# 11_iMX_8X_SPI_ADC.net
KiCad netlist of a schematic drawn in Altium Designer
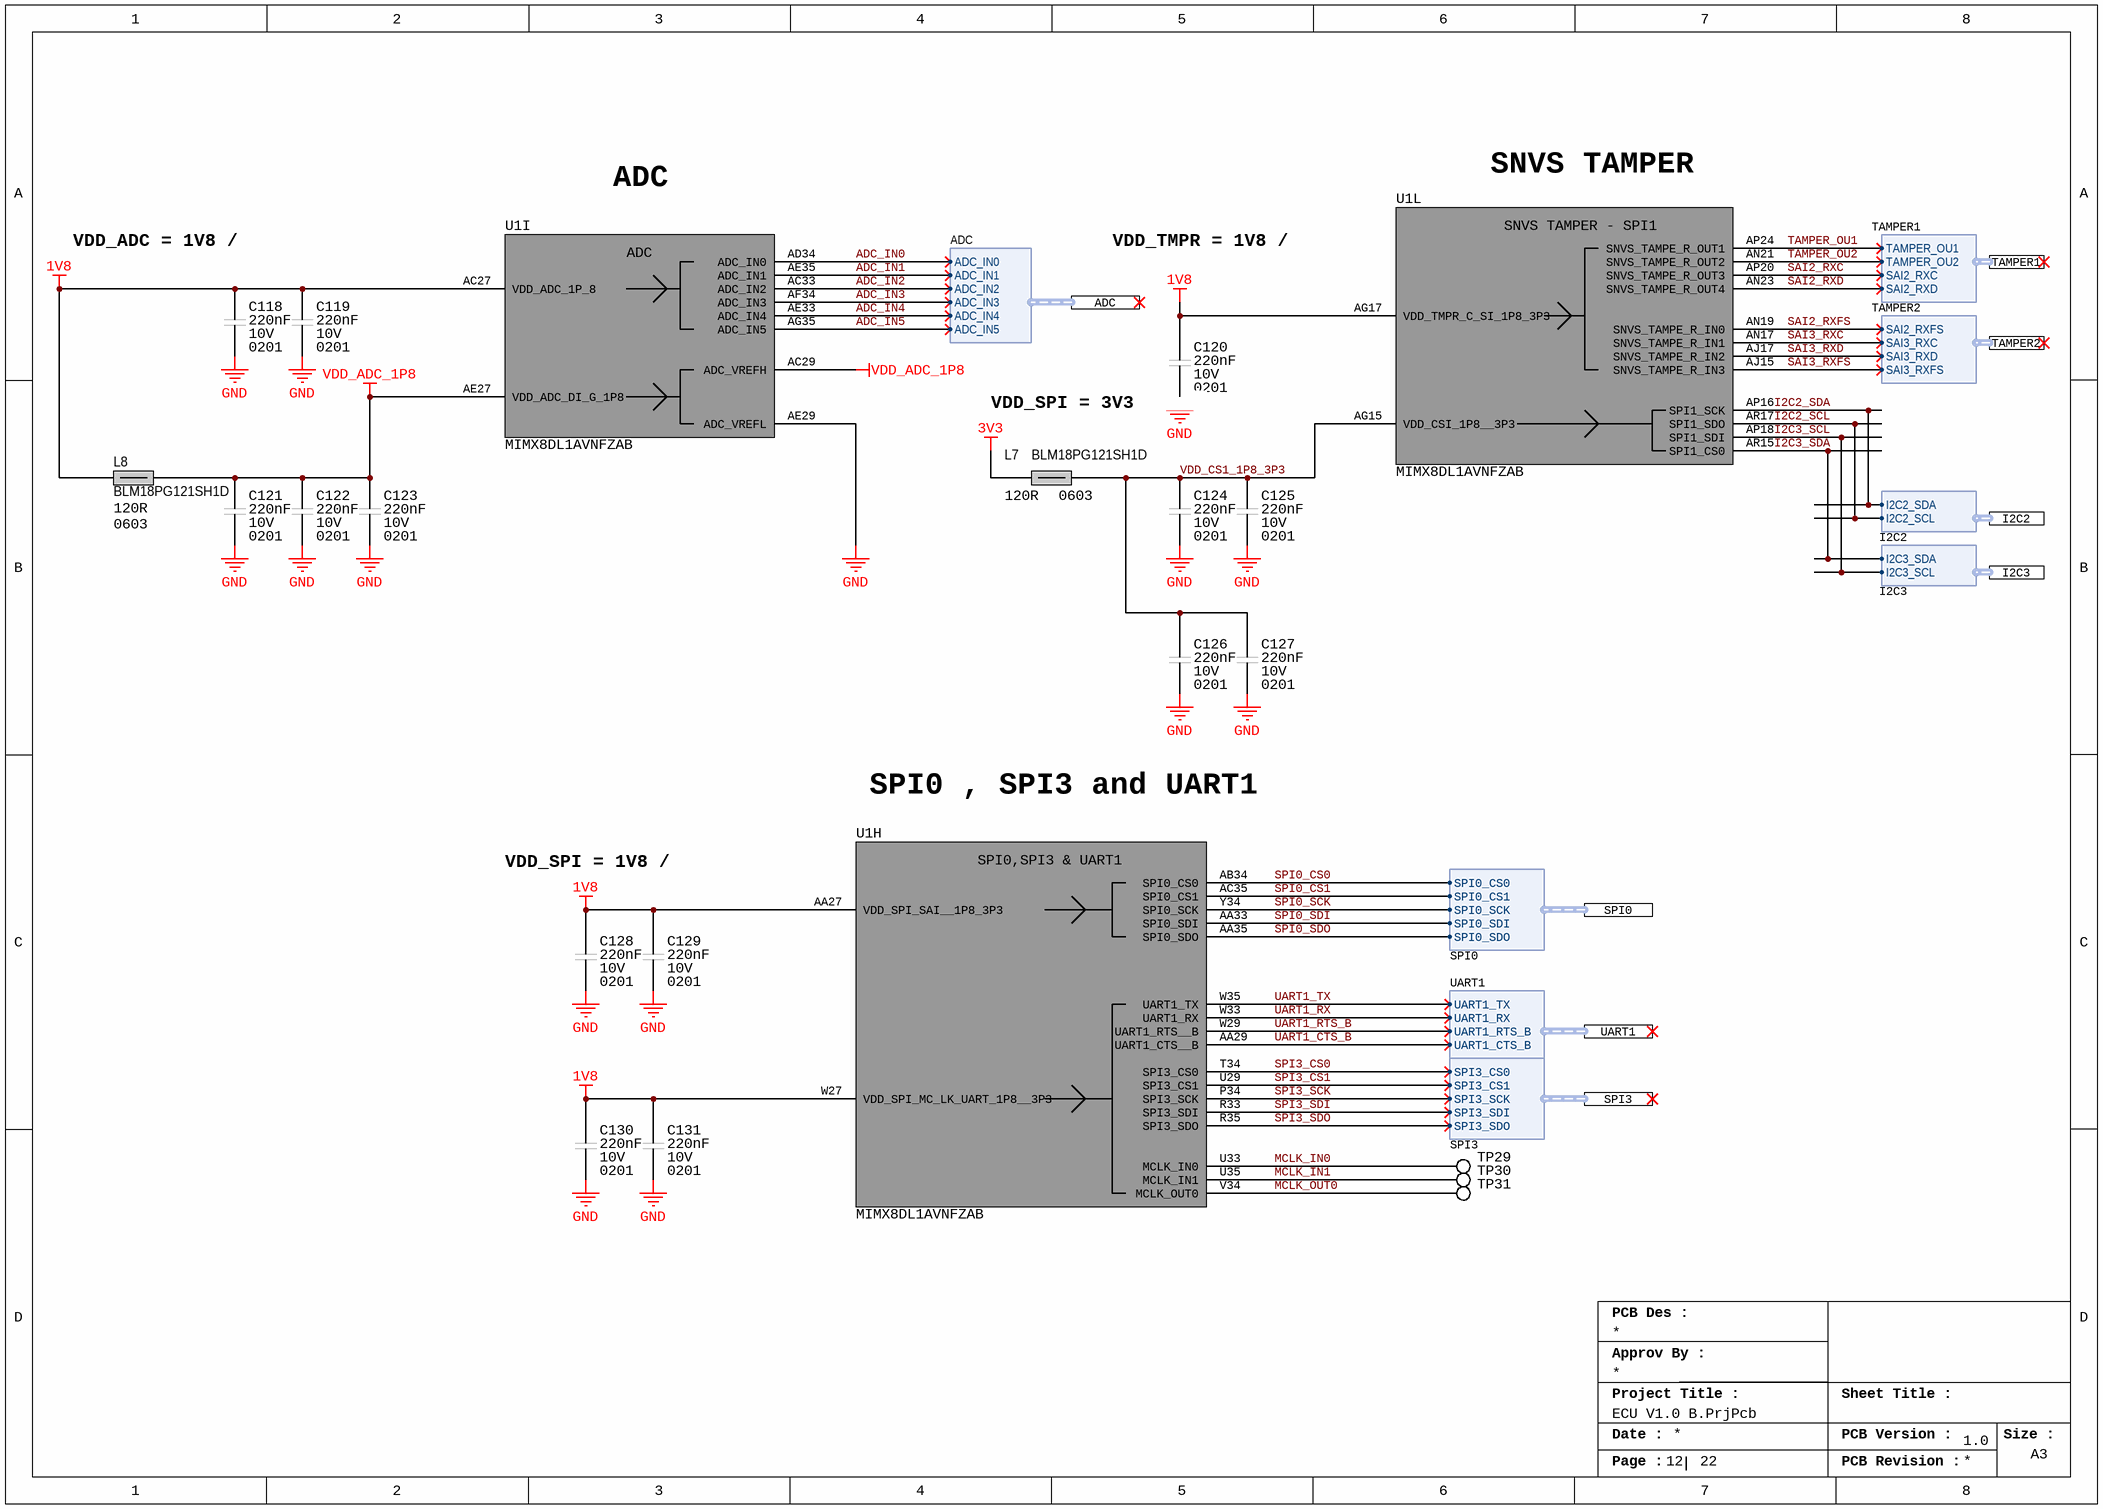
[diagram p0: 11_iMX 8X_SPI & ADC.SchDoc]

(export (version "E")
  (design (tool "Eeschema 10.0.6"))
  (components
    (comp (ref "C118")
      (value "LMK063BJ224MP-F")
      (footprint "CAP_0201_CAPC0603X03N")
      (description "Multilayer Ceramic Capacitors (High dielectric type), 10V, 0.22 uF, ± 20 %, 0201, X5R, RoHS")
      (fields
        (field (name "MANUFACTURER") "Taiyo Yuden")
        (field (name "TOLERANCE") "20%")
        (field (name "VOLTAGE RATING (DC)") "10V")
        (field (name "CAPACITANCE") "220nF")
        (field (name "CASE/PACKAGE") "0201")
      )
      (libsource (lib "Electronic Devices_LIB") (part "CAP_0.22UF_10V_X5R_0201"))
    )
    (comp (ref "C119")
      (value "LMK063BJ224MP-F")
      (footprint "CAP_0201_CAPC0603X03N")
      (description "Multilayer Ceramic Capacitors (High dielectric type), 10V, 0.22 uF, ± 20 %, 0201, X5R, RoHS")
      (fields
        (field (name "MANUFACTURER") "Taiyo Yuden")
        (field (name "TOLERANCE") "20%")
        (field (name "VOLTAGE RATING (DC)") "10V")
        (field (name "CAPACITANCE") "220nF")
        (field (name "CASE/PACKAGE") "0201")
      )
      (libsource (lib "Electronic Devices_LIB") (part "CAP_0.22UF_10V_X5R_0201"))
    )
    (comp (ref "C120")
      (value "LMK063BJ224MP-F")
      (footprint "CAP_0201_CAPC0603X03N")
      (description "Multilayer Ceramic Capacitors (High dielectric type), 10V, 0.22 uF, ± 20 %, 0201, X5R, RoHS")
      (fields
        (field (name "MANUFACTURER") "Taiyo Yuden")
        (field (name "TOLERANCE") "20%")
        (field (name "VOLTAGE RATING (DC)") "10V")
        (field (name "CAPACITANCE") "220nF")
        (field (name "CASE/PACKAGE") "0201")
      )
      (libsource (lib "Electronic Devices_LIB") (part "CAP_0.22UF_10V_X5R_0201"))
    )
    (comp (ref "C121")
      (value "LMK063BJ224MP-F")
      (footprint "CAP_0201_CAPC0603X03N")
      (description "Multilayer Ceramic Capacitors (High dielectric type), 10V, 0.22 uF, ± 20 %, 0201, X5R, RoHS")
      (fields
        (field (name "MANUFACTURER") "Taiyo Yuden")
        (field (name "TOLERANCE") "20%")
        (field (name "VOLTAGE RATING (DC)") "10V")
        (field (name "CAPACITANCE") "220nF")
        (field (name "CASE/PACKAGE") "0201")
      )
      (libsource (lib "Electronic Devices_LIB") (part "CAP_0.22UF_10V_X5R_0201"))
    )
    (comp (ref "C122")
      (value "LMK063BJ224MP-F")
      (footprint "CAP_0201_CAPC0603X03N")
      (description "Multilayer Ceramic Capacitors (High dielectric type), 10V, 0.22 uF, ± 20 %, 0201, X5R, RoHS")
      (fields
        (field (name "MANUFACTURER") "Taiyo Yuden")
        (field (name "TOLERANCE") "20%")
        (field (name "VOLTAGE RATING (DC)") "10V")
        (field (name "CAPACITANCE") "220nF")
        (field (name "CASE/PACKAGE") "0201")
      )
      (libsource (lib "Electronic Devices_LIB") (part "CAP_0.22UF_10V_X5R_0201"))
    )
    (comp (ref "C123")
      (value "LMK063BJ224MP-F")
      (footprint "CAP_0201_CAPC0603X03N")
      (description "Multilayer Ceramic Capacitors (High dielectric type), 10V, 0.22 uF, ± 20 %, 0201, X5R, RoHS")
      (fields
        (field (name "MANUFACTURER") "Taiyo Yuden")
        (field (name "TOLERANCE") "20%")
        (field (name "VOLTAGE RATING (DC)") "10V")
        (field (name "CAPACITANCE") "220nF")
        (field (name "CASE/PACKAGE") "0201")
      )
      (libsource (lib "Electronic Devices_LIB") (part "CAP_0.22UF_10V_X5R_0201"))
    )
    (comp (ref "C124")
      (value "LMK063BJ224MP-F")
      (footprint "CAP_0201_CAPC0603X03N")
      (description "Multilayer Ceramic Capacitors (High dielectric type), 10V, 0.22 uF, ± 20 %, 0201, X5R, RoHS")
      (fields
        (field (name "MANUFACTURER") "Taiyo Yuden")
        (field (name "TOLERANCE") "20%")
        (field (name "VOLTAGE RATING (DC)") "10V")
        (field (name "CAPACITANCE") "220nF")
        (field (name "CASE/PACKAGE") "0201")
      )
      (libsource (lib "Electronic Devices_LIB") (part "CAP_0.22UF_10V_X5R_0201"))
    )
    (comp (ref "C125")
      (value "LMK063BJ224MP-F")
      (footprint "CAP_0201_CAPC0603X03N")
      (description "Multilayer Ceramic Capacitors (High dielectric type), 10V, 0.22 uF, ± 20 %, 0201, X5R, RoHS")
      (fields
        (field (name "MANUFACTURER") "Taiyo Yuden")
        (field (name "TOLERANCE") "20%")
        (field (name "VOLTAGE RATING (DC)") "10V")
        (field (name "CAPACITANCE") "220nF")
        (field (name "CASE/PACKAGE") "0201")
      )
      (libsource (lib "Electronic Devices_LIB") (part "CAP_0.22UF_10V_X5R_0201"))
    )
    (comp (ref "C126")
      (value "LMK063BJ224MP-F")
      (footprint "CAP_0201_CAPC0603X03N")
      (description "Multilayer Ceramic Capacitors (High dielectric type), 10V, 0.22 uF, ± 20 %, 0201, X5R, RoHS")
      (fields
        (field (name "MANUFACTURER") "Taiyo Yuden")
        (field (name "TOLERANCE") "20%")
        (field (name "VOLTAGE RATING (DC)") "10V")
        (field (name "CAPACITANCE") "220nF")
        (field (name "CASE/PACKAGE") "0201")
      )
      (libsource (lib "Electronic Devices_LIB") (part "CAP_0.22UF_10V_X5R_0201"))
    )
    (comp (ref "C127")
      (value "LMK063BJ224MP-F")
      (footprint "CAP_0201_CAPC0603X03N")
      (description "Multilayer Ceramic Capacitors (High dielectric type), 10V, 0.22 uF, ± 20 %, 0201, X5R, RoHS")
      (fields
        (field (name "MANUFACTURER") "Taiyo Yuden")
        (field (name "TOLERANCE") "20%")
        (field (name "VOLTAGE RATING (DC)") "10V")
        (field (name "CAPACITANCE") "220nF")
        (field (name "CASE/PACKAGE") "0201")
      )
      (libsource (lib "Electronic Devices_LIB") (part "CAP_0.22UF_10V_X5R_0201"))
    )
    (comp (ref "C128")
      (value "LMK063BJ224MP-F")
      (footprint "CAP_0201_CAPC0603X03N")
      (description "Multilayer Ceramic Capacitors (High dielectric type), 10V, 0.22 uF, ± 20 %, 0201, X5R, RoHS")
      (fields
        (field (name "MANUFACTURER") "Taiyo Yuden")
        (field (name "TOLERANCE") "20%")
        (field (name "VOLTAGE RATING (DC)") "10V")
        (field (name "CAPACITANCE") "220nF")
        (field (name "CASE/PACKAGE") "0201")
      )
      (libsource (lib "Electronic Devices_LIB") (part "CAP_0.22UF_10V_X5R_0201"))
    )
    (comp (ref "C129")
      (value "LMK063BJ224MP-F")
      (footprint "CAP_0201_CAPC0603X03N")
      (description "Multilayer Ceramic Capacitors (High dielectric type), 10V, 0.22 uF, ± 20 %, 0201, X5R, RoHS")
      (fields
        (field (name "MANUFACTURER") "Taiyo Yuden")
        (field (name "TOLERANCE") "20%")
        (field (name "VOLTAGE RATING (DC)") "10V")
        (field (name "CAPACITANCE") "220nF")
        (field (name "CASE/PACKAGE") "0201")
      )
      (libsource (lib "Electronic Devices_LIB") (part "CAP_0.22UF_10V_X5R_0201"))
    )
    (comp (ref "C130")
      (value "LMK063BJ224MP-F")
      (footprint "CAP_0201_CAPC0603X03N")
      (description "Multilayer Ceramic Capacitors (High dielectric type), 10V, 0.22 uF, ± 20 %, 0201, X5R, RoHS")
      (fields
        (field (name "MANUFACTURER") "Taiyo Yuden")
        (field (name "TOLERANCE") "20%")
        (field (name "VOLTAGE RATING (DC)") "10V")
        (field (name "CAPACITANCE") "220nF")
        (field (name "CASE/PACKAGE") "0201")
      )
      (libsource (lib "Electronic Devices_LIB") (part "CAP_0.22UF_10V_X5R_0201"))
    )
    (comp (ref "C131")
      (value "LMK063BJ224MP-F")
      (footprint "CAP_0201_CAPC0603X03N")
      (description "Multilayer Ceramic Capacitors (High dielectric type), 10V, 0.22 uF, ± 20 %, 0201, X5R, RoHS")
      (fields
        (field (name "MANUFACTURER") "Taiyo Yuden")
        (field (name "TOLERANCE") "20%")
        (field (name "VOLTAGE RATING (DC)") "10V")
        (field (name "CAPACITANCE") "220nF")
        (field (name "CASE/PACKAGE") "0201")
      )
      (libsource (lib "Electronic Devices_LIB") (part "CAP_0.22UF_10V_X5R_0201"))
    )
    (comp (ref "L7")
      (value "BLM18PG121SH1D")
      (footprint "IND_0603_INDC1608X08N")
      (description "Ferrite Beads Multi-Layer 120Ohm 25% 100MHz 2A 50mOhm DCR 0603 Automotive Paper T/R")
      (fields
        (field (name "MANUFACTURER") "Murata")
        (field (name "TOLERANCE") "25%")
        (field (name "IMPEDANCE") "120R")
        (field (name "CASE/PACKAGE") "0603")
      )
      (libsource (lib "Electronic Devices_LIB") (part "IND_FERRITE_BEADS_120R_2A_0603_BLM18PG121SH1D"))
    )
    (comp (ref "L8")
      (value "BLM18PG121SH1D")
      (footprint "IND_0603_INDC1608X08N")
      (description "Ferrite Beads Multi-Layer 120Ohm 25% 100MHz 2A 50mOhm DCR 0603 Automotive Paper T/R")
      (fields
        (field (name "MANUFACTURER") "Murata")
        (field (name "TOLERANCE") "25%")
        (field (name "IMPEDANCE") "120R")
        (field (name "CASE/PACKAGE") "0603")
      )
      (libsource (lib "Electronic Devices_LIB") (part "IND_FERRITE_BEADS_120R_2A_0603_BLM18PG121SH1D"))
    )
    (comp (ref "TP29")
      (value "NO COMPONENT")
      (footprint "TP_PAD_0.5MM_SMD_ROUND")
      (description "Test Point, SMD pad, round, 1.5mm, 1.6mm, 3mm diameter")
      (libsource (lib "Electronic Devices_LIB") (part "TP_PAD_SMD_SMALL"))
    )
    (comp (ref "TP30")
      (value "NO COMPONENT")
      (footprint "TP_PAD_0.5MM_SMD_ROUND")
      (description "Test Point, SMD pad, round, 1.5mm, 1.6mm, 3mm diameter")
      (libsource (lib "Electronic Devices_LIB") (part "TP_PAD_SMD_SMALL"))
    )
    (comp (ref "TP31")
      (value "NO COMPONENT")
      (footprint "TP_PAD_0.5MM_SMD_ROUND")
      (description "Test Point, SMD pad, round, 1.5mm, 1.6mm, 3mm diameter")
      (libsource (lib "Electronic Devices_LIB") (part "TP_PAD_SMD_SMALL"))
    )
    (comp (ref "U1")
      (value "MIMX8DL1AVNFZAB")
      (footprint "MIMX8DL1AVNFZAB")
      (description "I.MX8 Dxl 15SQ / Tray Rohs Compliant: Yes")
      (fields (field (name "MANUFACTURER") "NXP Semiconductors"))
      (libsource (lib "Electronic Devices_LIB") (part "IC_MPU_ARM_1.2GHz_MIMX8DL1AVNFZAB"))
    )
  )
  (nets
    (net (code "9") (name "/ADC_IN0") (class "Default")
      (node (ref "U1") (pin "AD34") (pinfunction "ADC_IN0_AD34") (pintype "passive+no_connect"))
    )
    (net (code "10") (name "/ADC_IN1") (class "Default")
      (node (ref "U1") (pin "AE35") (pinfunction "ADC_IN1_AE35") (pintype "passive+no_connect"))
    )
    (net (code "11") (name "/ADC_IN2") (class "Default")
      (node (ref "U1") (pin "AC33") (pinfunction "ADC_IN2_AC33") (pintype "passive+no_connect"))
    )
    (net (code "12") (name "/ADC_IN3") (class "Default")
      (node (ref "U1") (pin "AF34") (pinfunction "ADC_IN3_AF34") (pintype "passive+no_connect"))
    )
    (net (code "13") (name "/ADC_IN4") (class "Default")
      (node (ref "U1") (pin "AE33") (pinfunction "ADC_IN4_AE33") (pintype "passive+no_connect"))
    )
    (net (code "14") (name "/ADC_IN5") (class "Default")
      (node (ref "U1") (pin "AG35") (pinfunction "ADC_IN5_AG35") (pintype "passive+no_connect"))
    )
    (net (code "15") (name "/I2C2_SCL") (class "Default")
      (node (ref "U1") (pin "AR17") (pinfunction "SPI1_SDO_AR17") (pintype "passive"))
    )
    (net (code "16") (name "/I2C2_SDA") (class "Default")
      (node (ref "U1") (pin "AP16") (pinfunction "SPI1_SCK_AP16") (pintype "passive"))
    )
    (net (code "17") (name "/I2C3_SCL") (class "Default")
      (node (ref "U1") (pin "AP18") (pinfunction "SPI1_SDI_AP18") (pintype "passive"))
    )
    (net (code "18") (name "/I2C3_SDA") (class "Default")
      (node (ref "U1") (pin "AR15") (pinfunction "SPI1_CS0_AR15") (pintype "passive"))
    )
    (net (code "19") (name "/MCLK_IN0") (class "Default")
      (node (ref "TP29") (pin "1") (pinfunction "1_1") (pintype "passive"))
      (node (ref "U1") (pin "U33") (pinfunction "MCLK_IN0_U33") (pintype "passive"))
    )
    (net (code "20") (name "/MCLK_IN1") (class "Default")
      (node (ref "TP30") (pin "1") (pinfunction "1_1") (pintype "passive"))
      (node (ref "U1") (pin "U35") (pinfunction "MCLK_IN1_U35") (pintype "passive"))
    )
    (net (code "21") (name "/MCLK_OUT0") (class "Default")
      (node (ref "TP31") (pin "1") (pinfunction "1_1") (pintype "passive"))
      (node (ref "U1") (pin "V34") (pinfunction "MCLK_OUT0_V34") (pintype "passive"))
    )
    (net (code "22") (name "/SAI2_RXC") (class "Default")
      (node (ref "U1") (pin "AP20") (pinfunction "SNVS_TAMPE_R_OUT3_AP20") (pintype "passive+no_connect"))
    )
    (net (code "23") (name "/SAI2_RXD") (class "Default")
      (node (ref "U1") (pin "AN23") (pinfunction "SNVS_TAMPE_R_OUT4_AN23") (pintype "passive+no_connect"))
    )
    (net (code "24") (name "/SAI2_RXFS") (class "Default")
      (node (ref "U1") (pin "AN19") (pinfunction "SNVS_TAMPE_R_IN0_AN19") (pintype "passive+no_connect"))
    )
    (net (code "25") (name "/SAI3_RXC") (class "Default")
      (node (ref "U1") (pin "AN17") (pinfunction "SNVS_TAMPE_R_IN1_AN17") (pintype "passive+no_connect"))
    )
    (net (code "26") (name "/SAI3_RXD") (class "Default")
      (node (ref "U1") (pin "AJ17") (pinfunction "SNVS_TAMPE_R_IN2_AJ17") (pintype "passive+no_connect"))
    )
    (net (code "27") (name "/SAI3_RXFS") (class "Default")
      (node (ref "U1") (pin "AJ15") (pinfunction "SNVS_TAMPE_R_IN3_AJ15") (pintype "passive+no_connect"))
    )
    (net (code "28") (name "/SPI0_CS0") (class "Default")
      (node (ref "U1") (pin "AB34") (pinfunction "SPI0_CS0_AB34") (pintype "passive"))
    )
    (net (code "29") (name "/SPI0_CS1") (class "Default")
      (node (ref "U1") (pin "AC35") (pinfunction "SPI0_CS1_AC35") (pintype "passive"))
    )
    (net (code "30") (name "/SPI0_SCK") (class "Default")
      (node (ref "U1") (pin "Y34") (pinfunction "SPI0_SCK_Y34") (pintype "passive"))
    )
    (net (code "31") (name "/SPI0_SDI") (class "Default")
      (node (ref "U1") (pin "AA33") (pinfunction "SPI0_SDI_AA33") (pintype "passive"))
    )
    (net (code "32") (name "/SPI0_SDO") (class "Default")
      (node (ref "U1") (pin "AA35") (pinfunction "SPI0_SDO_AA35") (pintype "passive"))
    )
    (net (code "33") (name "/SPI3_CS0") (class "Default")
      (node (ref "U1") (pin "T34") (pinfunction "SPI3_CS0_T34") (pintype "passive+no_connect"))
    )
    (net (code "34") (name "/SPI3_CS1") (class "Default")
      (node (ref "U1") (pin "U29") (pinfunction "SPI3_CS1_U29") (pintype "passive+no_connect"))
    )
    (net (code "35") (name "/SPI3_SCK") (class "Default")
      (node (ref "U1") (pin "P34") (pinfunction "SPI3_SCK_P34") (pintype "passive+no_connect"))
    )
    (net (code "36") (name "/SPI3_SDI") (class "Default")
      (node (ref "U1") (pin "R33") (pinfunction "SPI3_SDI_R33") (pintype "passive+no_connect"))
    )
    (net (code "37") (name "/SPI3_SDO") (class "Default")
      (node (ref "U1") (pin "R35") (pinfunction "SPI3_SDO_R35") (pintype "passive+no_connect"))
    )
    (net (code "38") (name "/TAMPER_OU1") (class "Default")
      (node (ref "U1") (pin "AP24") (pinfunction "SNVS_TAMPE_R_OUT1_AP24") (pintype "passive+no_connect"))
    )
    (net (code "39") (name "/TAMPER_OU2") (class "Default")
      (node (ref "U1") (pin "AN21") (pinfunction "SNVS_TAMPE_R_OUT2_AN21") (pintype "passive+no_connect"))
    )
    (net (code "40") (name "/UART1_CTS_B") (class "Default")
      (node (ref "U1") (pin "AA29") (pinfunction "UART1_CTS__B_AA29") (pintype "passive+no_connect"))
    )
    (net (code "41") (name "/UART1_RTS_B") (class "Default")
      (node (ref "U1") (pin "W29") (pinfunction "UART1_RTS__B_W29") (pintype "passive+no_connect"))
    )
    (net (code "42") (name "/UART1_RX") (class "Default")
      (node (ref "U1") (pin "W33") (pinfunction "UART1_RX_W33") (pintype "passive+no_connect"))
    )
    (net (code "43") (name "/UART1_TX") (class "Default")
      (node (ref "U1") (pin "W35") (pinfunction "UART1_TX_W35") (pintype "passive+no_connect"))
    )
    (net (code "45") (name "/VDD_CS1_1P8_3P3") (class "Default")
      (node (ref "C124") (pin "2") (pinfunction "2_2") (pintype "passive"))
      (node (ref "C125") (pin "2") (pinfunction "2_2") (pintype "passive"))
      (node (ref "C126") (pin "2") (pinfunction "2_2") (pintype "passive"))
      (node (ref "C127") (pin "2") (pinfunction "2_2") (pintype "passive"))
      (node (ref "L7") (pin "2") (pinfunction "2_2") (pintype "passive"))
      (node (ref "U1") (pin "AG15") (pinfunction "VDD_CSI_1P8__3P3_AG15") (pintype "passive"))
    )
    (net (code "53") (name "1V8") (class "Default")
      (node (ref "C118") (pin "2") (pinfunction "2_2") (pintype "passive"))
      (node (ref "C119") (pin "2") (pinfunction "2_2") (pintype "passive"))
      (node (ref "C120") (pin "2") (pinfunction "2_2") (pintype "passive"))
      (node (ref "C128") (pin "2") (pinfunction "2_2") (pintype "passive"))
      (node (ref "C129") (pin "2") (pinfunction "2_2") (pintype "passive"))
      (node (ref "C130") (pin "2") (pinfunction "2_2") (pintype "passive"))
      (node (ref "C131") (pin "2") (pinfunction "2_2") (pintype "passive"))
      (node (ref "L8") (pin "1") (pinfunction "1_1") (pintype "passive"))
      (node (ref "U1") (pin "AA27") (pinfunction "VDD_SPI_SAI__1P8_3P3_AA27") (pintype "passive"))
      (node (ref "U1") (pin "AC27") (pinfunction "VDD_ADC_1P_8_AC27") (pintype "passive"))
      (node (ref "U1") (pin "AG17") (pinfunction "VDD_TMPR_C_SI_1P8_3P3_AG17") (pintype "passive"))
      (node (ref "U1") (pin "W27") (pinfunction "VDD_SPI_MC_LK_UART_1P8__3P3_W27") (pintype "passive"))
    )
    (net (code "54") (name "3V3") (class "Default")
      (node (ref "L7") (pin "1") (pinfunction "1_1") (pintype "passive"))
    )
    (net (code "55") (name "GND") (class "Default")
      (node (ref "C118") (pin "1") (pinfunction "1_1") (pintype "passive"))
      (node (ref "C119") (pin "1") (pinfunction "1_1") (pintype "passive"))
      (node (ref "C120") (pin "1") (pinfunction "1_1") (pintype "passive"))
      (node (ref "C121") (pin "1") (pinfunction "1_1") (pintype "passive"))
      (node (ref "C122") (pin "1") (pinfunction "1_1") (pintype "passive"))
      (node (ref "C123") (pin "1") (pinfunction "1_1") (pintype "passive"))
      (node (ref "C124") (pin "1") (pinfunction "1_1") (pintype "passive"))
      (node (ref "C125") (pin "1") (pinfunction "1_1") (pintype "passive"))
      (node (ref "C126") (pin "1") (pinfunction "1_1") (pintype "passive"))
      (node (ref "C127") (pin "1") (pinfunction "1_1") (pintype "passive"))
      (node (ref "C128") (pin "1") (pinfunction "1_1") (pintype "passive"))
      (node (ref "C129") (pin "1") (pinfunction "1_1") (pintype "passive"))
      (node (ref "C130") (pin "1") (pinfunction "1_1") (pintype "passive"))
      (node (ref "C131") (pin "1") (pinfunction "1_1") (pintype "passive"))
      (node (ref "U1") (pin "AE29") (pinfunction "ADC_VREFL_AE29") (pintype "passive"))
    )
    (net (code "56") (name "VDD_ADC_1P8") (class "Default")
      (node (ref "C121") (pin "2") (pinfunction "2_2") (pintype "passive"))
      (node (ref "C122") (pin "2") (pinfunction "2_2") (pintype "passive"))
      (node (ref "C123") (pin "2") (pinfunction "2_2") (pintype "passive"))
      (node (ref "L8") (pin "2") (pinfunction "2_2") (pintype "passive"))
      (node (ref "U1") (pin "AC29") (pinfunction "ADC_VREFH_AC29") (pintype "passive"))
      (node (ref "U1") (pin "AE27") (pinfunction "VDD_ADC_DI_G_1P8_AE27") (pintype "passive"))
    )
  )
)
